# SCH.net
KiCad netlist of a schematic drawn in EasyEDA
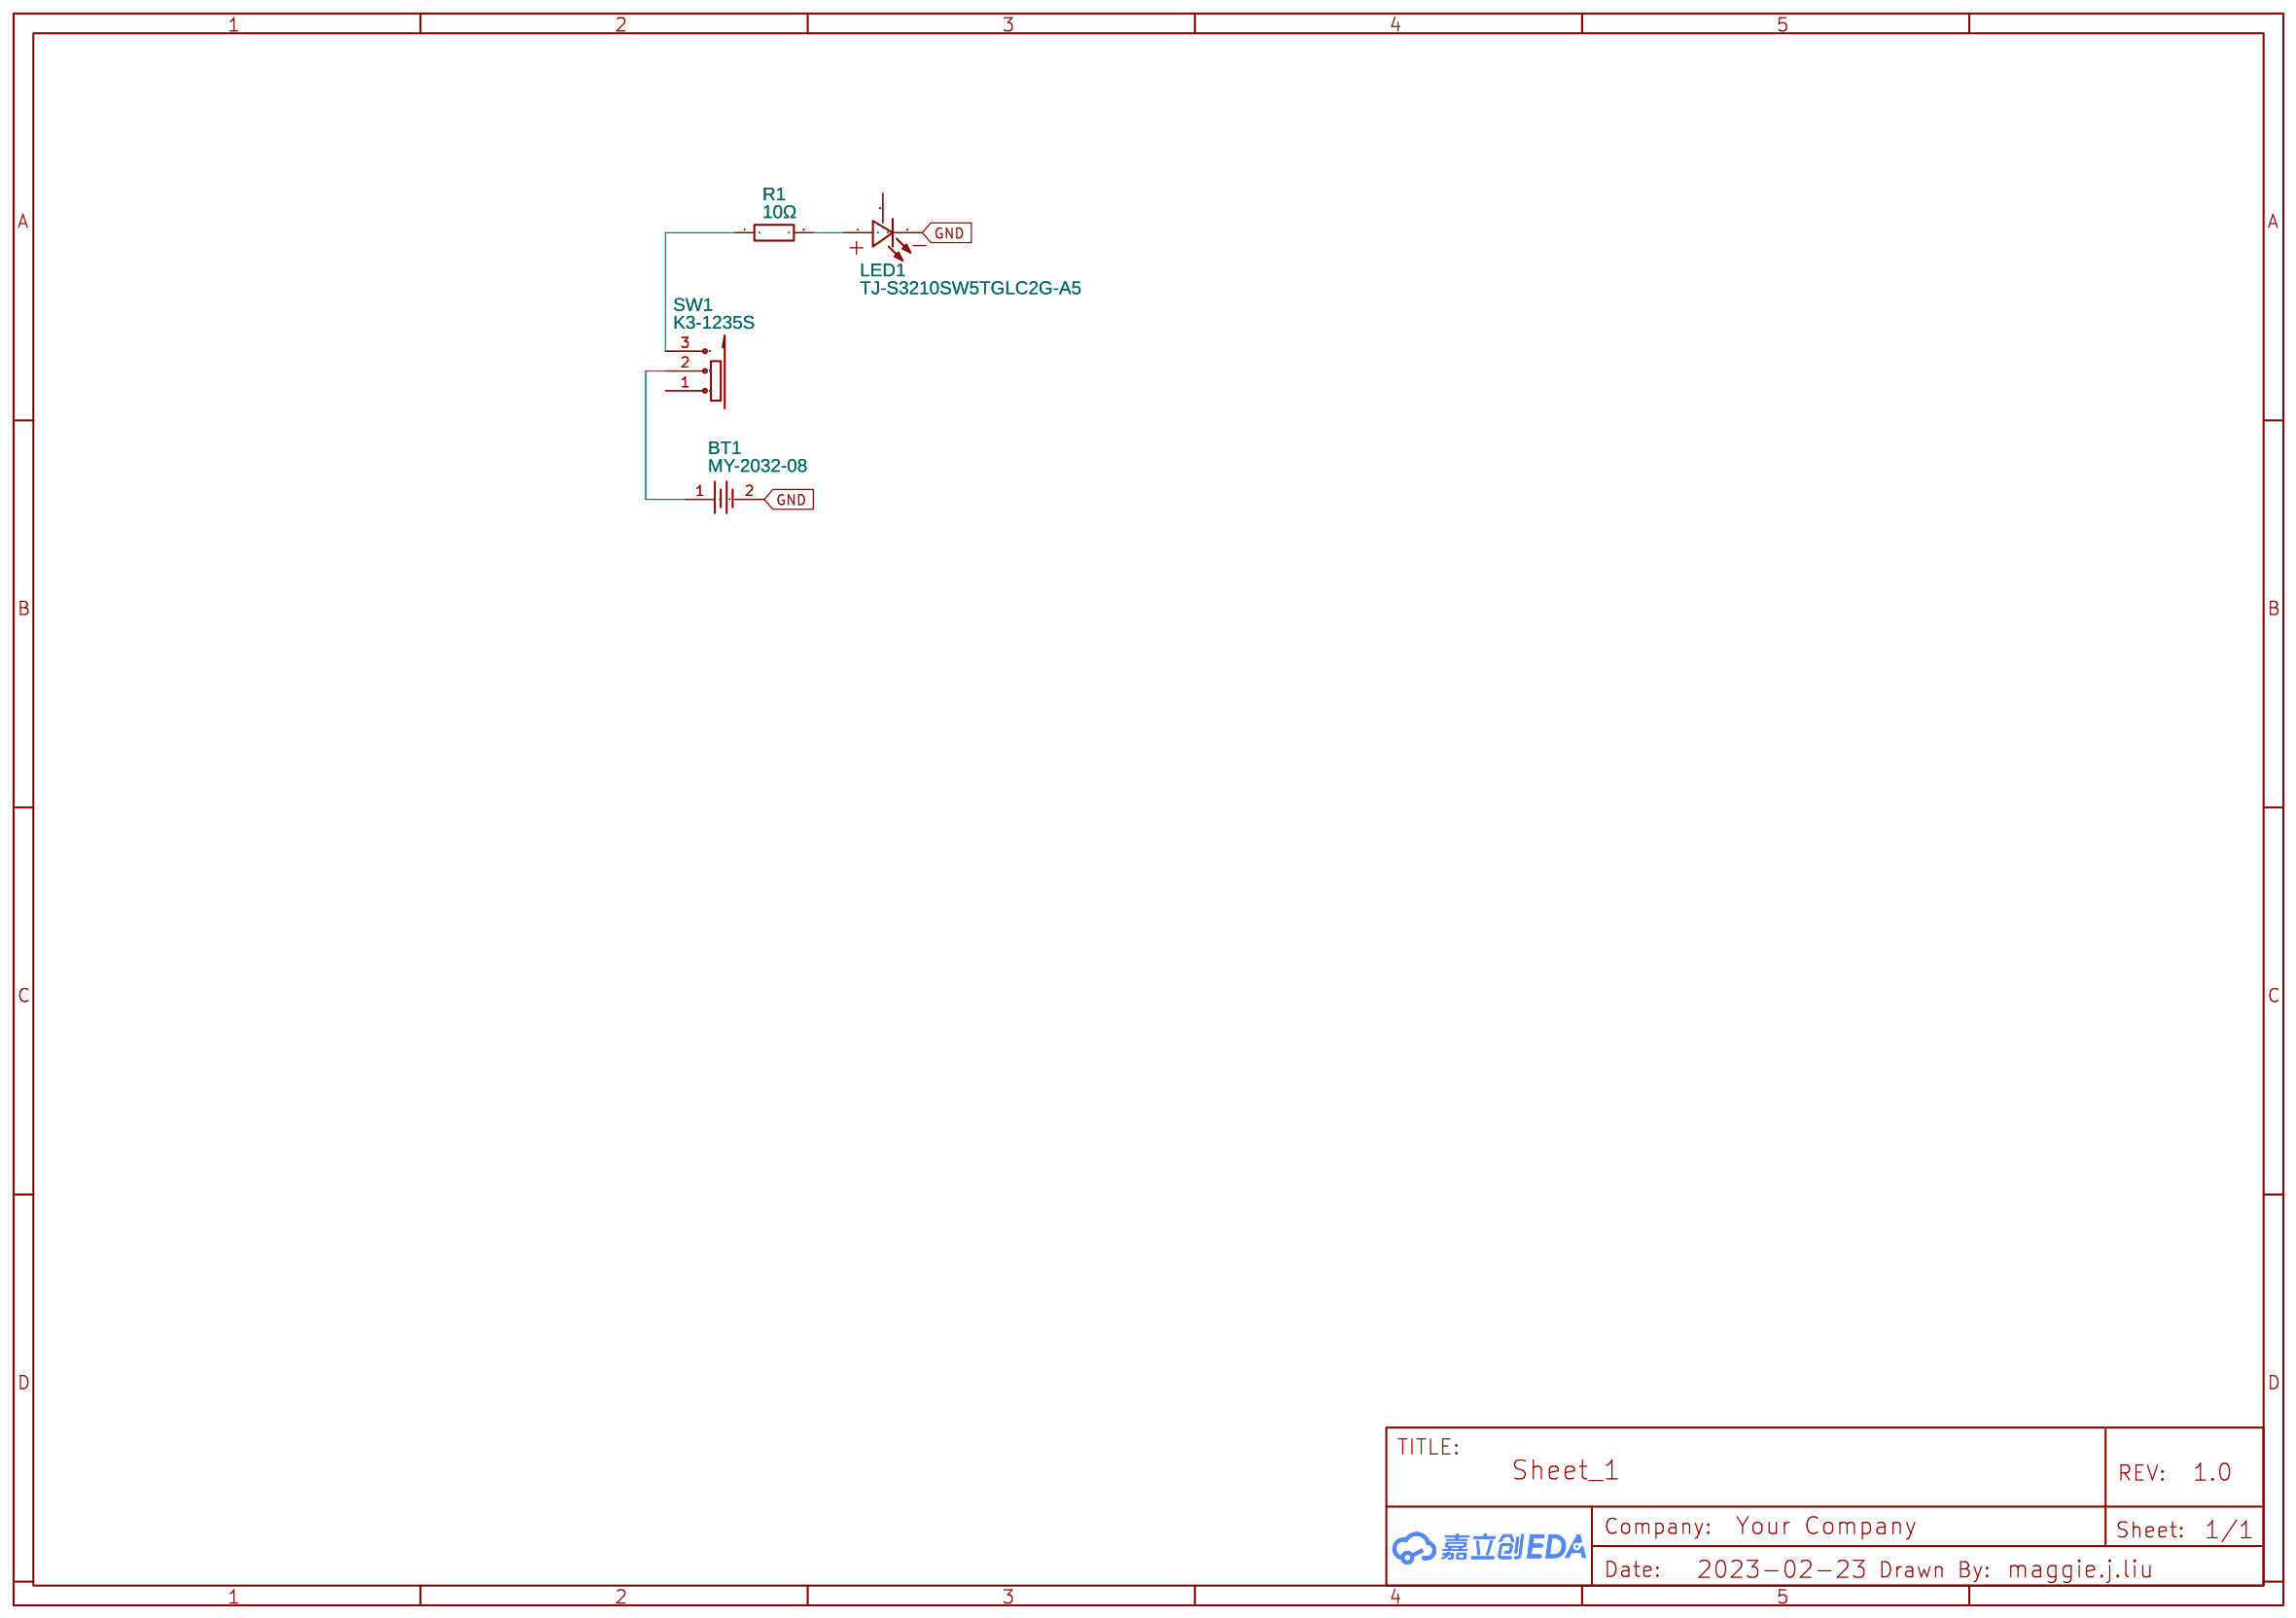
[diagram p0: schematic sheet]

(export (version "E")
  (design (tool "Eeschema 10.0.6"))
  (components
    (comp (ref "BT1")
      (value "MY-2032-08")
      (fields (field (name "BOM_Supplier Part") "C964831"))
      (libsource (lib "") (part "MY-2032-08"))
    )
    (comp (ref "LED1")
      (value "TJ-S3210SW5TGLC2G-A5")
      (fields (field (name "BOM_Supplier Part") "C273630"))
      (libsource (lib "") (part "TJ-S3210SW5TGLC2G-A5"))
    )
    (comp (ref "R1")
      (value "10Ω")
      (fields
        (field (name "BOM_Manufacturer Part") "0603WAF100JT5E")
        (field (name "BOM_Supplier Part") "C22859")
      )
      (libsource (lib "") (part "0603WAF100JT5E"))
    )
    (comp (ref "SW1")
      (value "K3-1235S")
      (fields
        (field (name "BOM_Manufacturer Part") "K3-1235S-F1")
        (field (name "BOM_Supplier Part") "C92660")
      )
      (libsource (lib "") (part "K3-1235S"))
    )
  )
  (nets
    (net (code "1") (name "GND") (class "Default")
      (node (ref "BT1") (pin "2") (pinfunction "2_2") (pintype "input"))
      (node (ref "LED1") (pin "1") (pinfunction "1_1") (pintype "unspecified"))
    )
    (net (code "2") (name "Net-(BT1-Pad1)") (class "Default")
      (node (ref "BT1") (pin "1") (pinfunction "1_1") (pintype "input"))
      (node (ref "SW1") (pin "2") (pinfunction "2_2") (pintype "unspecified"))
    )
    (net (code "3") (name "Net-(LED1-Pad2)") (class "Default")
      (node (ref "LED1") (pin "2") (pinfunction "2_2") (pintype "unspecified"))
      (node (ref "R1") (pin "2") (pinfunction "2_2") (pintype "input"))
    )
    (net (code "4") (name "Net-(R1-Pad1)") (class "Default")
      (node (ref "R1") (pin "1") (pinfunction "1_1") (pintype "input"))
      (node (ref "SW1") (pin "3") (pinfunction "3_3") (pintype "unspecified"))
    )
    (net (code "5") (name "unconnected-(LED1-Pad3)") (class "Default")
      (node (ref "LED1") (pin "3") (pinfunction "3_3") (pintype "unspecified"))
    )
    (net (code "6") (name "unconnected-(SW1-Pad1)") (class "Default")
      (node (ref "SW1") (pin "1") (pinfunction "1_1") (pintype "unspecified"))
    )
  )
)
